# ESP_Server.net
KiCad netlist of a schematic drawn in EasyEDA
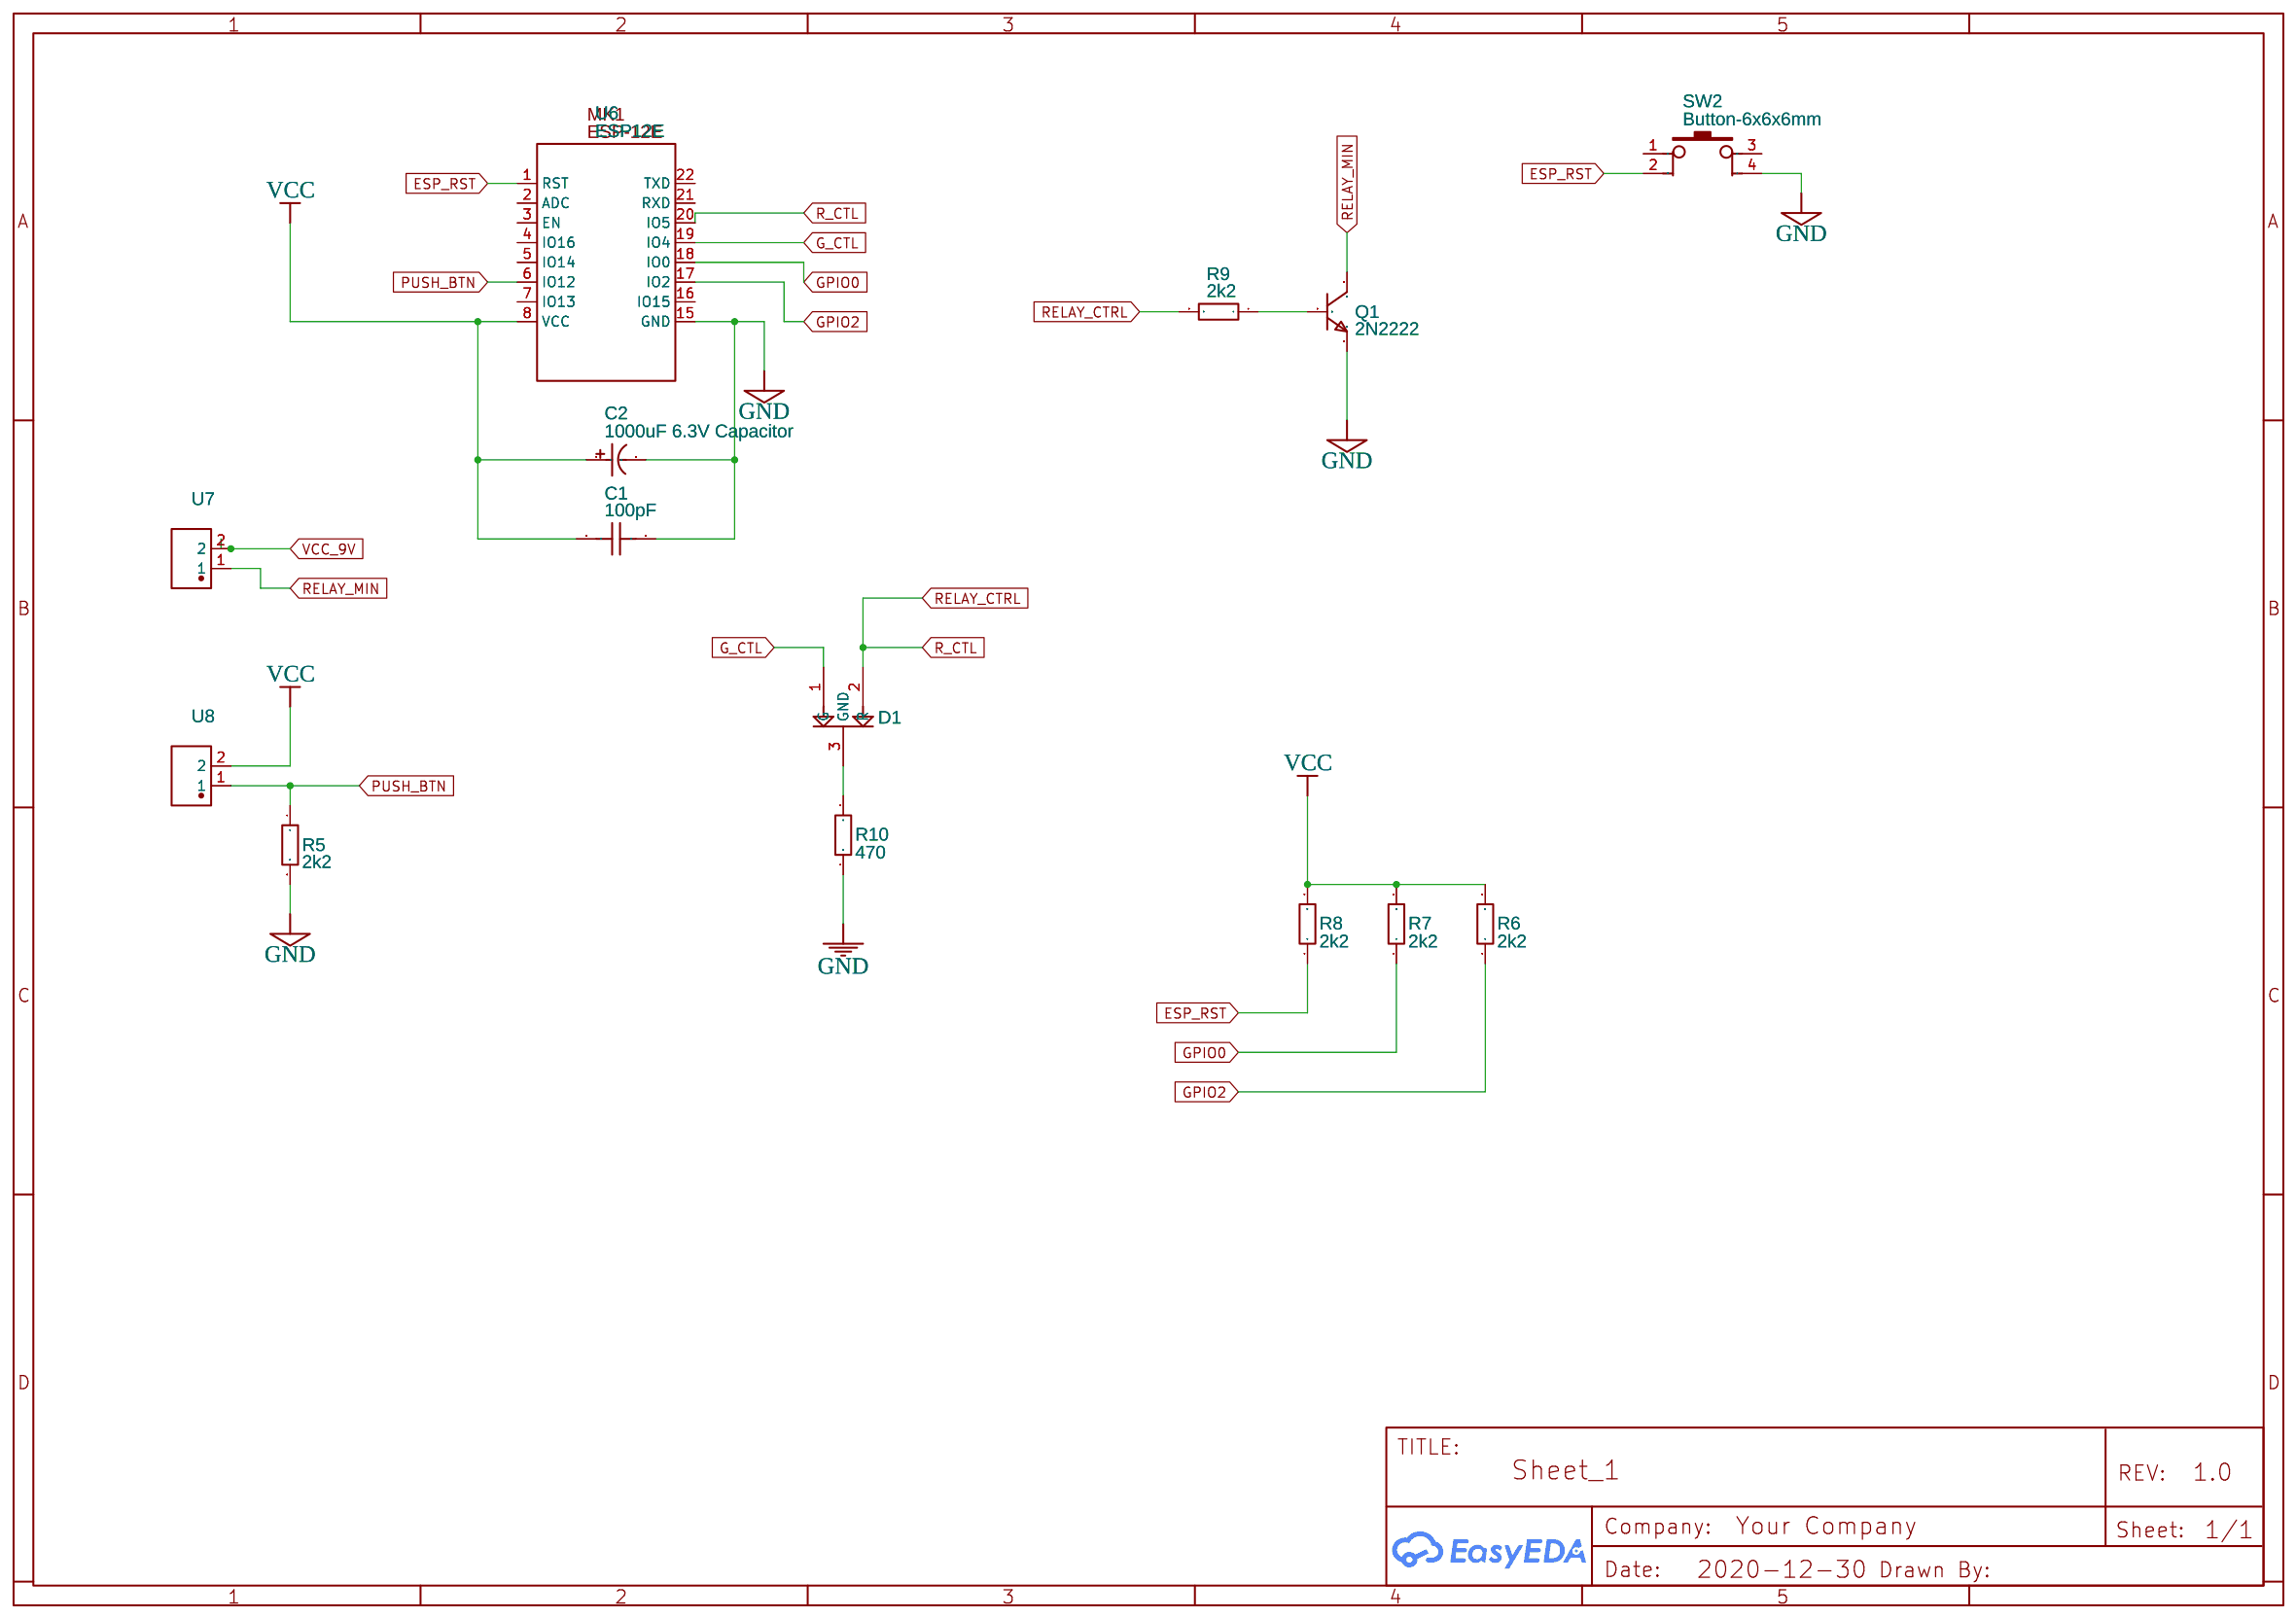
[diagram p0: schematic sheet]

(export (version "E")
  (design (tool "Eeschema 10.0.6"))
  (components
    (comp (ref "C1")
      (value "100pF")
      (fields
        (field (name "BOM_Manufacturer Part") "CC1H101KC74DSL4B10MN")
        (field (name "BOM_Supplier Part") "C254079")
      )
      (libsource (lib "") (part "CC1H101KC74DSL4B10MN"))
    )
    (comp (ref "C2") (value "1000uF 6.3V Capacitor") (libsource (lib "") (part "1000uF 6.3V Capacitor")))
    (comp (ref "D1")
      (value "RED GREEN CATODO")
      (fields (field (name "BOM_Manufacturer Part") "RG309WK-C"))
      (libsource (lib "") (part "RED GREEN CATODO"))
    )
    (comp (ref "Q1")
      (value "2N2222")
      (fields (field (name "BOM_Supplier Part") "C118536"))
      (libsource (lib "") (part "2N2222"))
    )
    (comp (ref "R5")
      (value "2k2")
      (fields
        (field (name "BOM_Manufacturer Part") "CFR02SJ0220A10")
        (field (name "BOM_Supplier Part") "C69874")
      )
      (libsource (lib "") (part "2k2_2"))
    )
    (comp (ref "R6")
      (value "2k2")
      (fields
        (field (name "BOM_Manufacturer Part") "CFR02SJ0220A10")
        (field (name "BOM_Supplier Part") "C69874")
      )
      (libsource (lib "") (part "2k2_1"))
    )
    (comp (ref "R7")
      (value "2k2")
      (fields
        (field (name "BOM_Manufacturer Part") "CFR02SJ0220A10")
        (field (name "BOM_Supplier Part") "C69874")
      )
      (libsource (lib "") (part "2k2_1"))
    )
    (comp (ref "R8")
      (value "2k2")
      (fields
        (field (name "BOM_Manufacturer Part") "CFR02SJ0220A10")
        (field (name "BOM_Supplier Part") "C69874")
      )
      (libsource (lib "") (part "2k2_1"))
    )
    (comp (ref "R9")
      (value "2k2")
      (fields
        (field (name "BOM_Manufacturer Part") "CFR02SJ0220A10")
        (field (name "BOM_Supplier Part") "C69874")
      )
      (libsource (lib "") (part "2k2"))
    )
    (comp (ref "R10")
      (value "470")
      (fields
        (field (name "BOM_Manufacturer Part") "MFR0W4F4700A50")
        (field (name "BOM_Supplier Part") "C58592")
      )
      (libsource (lib "") (part "47Ω"))
    )
    (comp (ref "SW2")
      (value "Button-6x6x6mm")
      (fields
        (field (name "BOM_Manufacturer Part") "Switch,6*6*6Plastic head,260G, 0.25mm,Straight line")
        (field (name "BOM_Supplier Part") "C71836")
      )
      (libsource (lib "") (part "Button-6x6x6mm"))
    )
    (comp (ref "U6") (value "ESP12E") (libsource (lib "") (part "ESP12E")))
    (comp (ref "U7")
      (value "XY301V-A-5.0-2P")
      (fields (field (name "BOM_Supplier Part") "C557651"))
      (libsource (lib "") (part "XY301V-A-5.0-2P"))
    )
    (comp (ref "U8")
      (value "XY301V-A-5.0-2P")
      (fields (field (name "BOM_Supplier Part") "C557651"))
      (libsource (lib "") (part "XY301V-A-5.0-2P"))
    )
  )
  (nets
    (net (code "1") (name "ESP_RST") (class "Default")
      (node (ref "R8") (pin "1") (pinfunction "1_1") (pintype "input"))
      (node (ref "SW2") (pin "2") (pinfunction "2_2") (pintype "input"))
      (node (ref "U6") (pin "1") (pinfunction "RST_1") (pintype "unspecified"))
    )
    (net (code "2") (name "GND") (class "Default")
      (node (ref "C1") (pin "2") (pinfunction "2_2") (pintype "unspecified"))
      (node (ref "C2") (pin "2") (pinfunction "2_2") (pintype "input"))
      (node (ref "Q1") (pin "1") (pinfunction "E_1") (pintype "unspecified"))
      (node (ref "R10") (pin "1") (pinfunction "1_1") (pintype "input"))
      (node (ref "R5") (pin "2") (pinfunction "2_2") (pintype "input"))
      (node (ref "SW2") (pin "4") (pinfunction "4_4") (pintype "input"))
      (node (ref "U6") (pin "15") (pinfunction "GND_15") (pintype "unspecified"))
    )
    (net (code "3") (name "GPIO0") (class "Default")
      (node (ref "R7") (pin "1") (pinfunction "1_1") (pintype "input"))
      (node (ref "U6") (pin "18") (pinfunction "IO0_18") (pintype "unspecified"))
    )
    (net (code "4") (name "GPIO2") (class "Default")
      (node (ref "R6") (pin "1") (pinfunction "1_1") (pintype "input"))
      (node (ref "U6") (pin "17") (pinfunction "IO2_17") (pintype "unspecified"))
    )
    (net (code "5") (name "G_CTL") (class "Default")
      (node (ref "D1") (pin "1") (pinfunction "G_1") (pintype "unspecified"))
      (node (ref "U6") (pin "19") (pinfunction "IO4_19") (pintype "unspecified"))
    )
    (net (code "6") (name "Net-(D1-GND)") (class "Default")
      (node (ref "D1") (pin "3") (pinfunction "GND_3") (pintype "unspecified"))
      (node (ref "R10") (pin "2") (pinfunction "2_2") (pintype "input"))
    )
    (net (code "7") (name "Net-(Q1-B)") (class "Default")
      (node (ref "Q1") (pin "2") (pinfunction "B_2") (pintype "unspecified"))
      (node (ref "R9") (pin "1") (pinfunction "1_1") (pintype "input"))
    )
    (net (code "8") (name "PUSH_BTN") (class "Default")
      (node (ref "R5") (pin "1") (pinfunction "1_1") (pintype "input"))
      (node (ref "U6") (pin "6") (pinfunction "IO12_6") (pintype "unspecified"))
      (node (ref "U8") (pin "1") (pinfunction "1_1") (pintype "unspecified"))
    )
    (net (code "9") (name "RELAY_CTRL") (class "Default")
      (node (ref "D1") (pin "2") (pinfunction "R_2") (pintype "unspecified"))
      (node (ref "R9") (pin "2") (pinfunction "2_2") (pintype "input"))
      (node (ref "U6") (pin "20") (pinfunction "IO5_20") (pintype "unspecified"))
    )
    (net (code "10") (name "RELAY_MIN") (class "Default")
      (node (ref "Q1") (pin "3") (pinfunction "C_3") (pintype "unspecified"))
      (node (ref "U7") (pin "1") (pinfunction "1_1") (pintype "unspecified"))
    )
    (net (code "11") (name "VCC") (class "Default")
      (node (ref "C1") (pin "1") (pinfunction "1_1") (pintype "unspecified"))
      (node (ref "C2") (pin "1") (pinfunction "1_1") (pintype "input"))
      (node (ref "R6") (pin "2") (pinfunction "2_2") (pintype "input"))
      (node (ref "R7") (pin "2") (pinfunction "2_2") (pintype "input"))
      (node (ref "R8") (pin "2") (pinfunction "2_2") (pintype "input"))
      (node (ref "U6") (pin "8") (pinfunction "VCC_8") (pintype "unspecified"))
      (node (ref "U8") (pin "2") (pinfunction "2_2") (pintype "unspecified"))
    )
    (net (code "12") (name "VCC_9V") (class "Default")
      (node (ref "U7") (pin "2") (pinfunction "2_2") (pintype "unspecified"))
    )
    (net (code "13") (name "unconnected-(SW2-Pad1)") (class "Default")
      (node (ref "SW2") (pin "1") (pinfunction "1_1") (pintype "input"))
    )
    (net (code "14") (name "unconnected-(SW2-Pad3)") (class "Default")
      (node (ref "SW2") (pin "3") (pinfunction "3_3") (pintype "input"))
    )
    (net (code "15") (name "unconnected-(U6-ADC-Pad2)") (class "Default")
      (node (ref "U6") (pin "2") (pinfunction "ADC_2") (pintype "unspecified"))
    )
    (net (code "16") (name "unconnected-(U6-EN-Pad3)") (class "Default")
      (node (ref "U6") (pin "3") (pinfunction "EN_3") (pintype "unspecified"))
    )
    (net (code "17") (name "unconnected-(U6-IO13-Pad7)") (class "Default")
      (node (ref "U6") (pin "7") (pinfunction "IO13_7") (pintype "unspecified"))
    )
    (net (code "18") (name "unconnected-(U6-IO14-Pad5)") (class "Default")
      (node (ref "U6") (pin "5") (pinfunction "IO14_5") (pintype "unspecified"))
    )
    (net (code "19") (name "unconnected-(U6-IO15-Pad16)") (class "Default")
      (node (ref "U6") (pin "16") (pinfunction "IO15_16") (pintype "unspecified"))
    )
    (net (code "20") (name "unconnected-(U6-IO16-Pad4)") (class "Default")
      (node (ref "U6") (pin "4") (pinfunction "IO16_4") (pintype "unspecified"))
    )
    (net (code "21") (name "unconnected-(U6-RXD-Pad21)") (class "Default")
      (node (ref "U6") (pin "21") (pinfunction "RXD_21") (pintype "unspecified"))
    )
    (net (code "22") (name "unconnected-(U6-TXD-Pad22)") (class "Default")
      (node (ref "U6") (pin "22") (pinfunction "TXD_22") (pintype "unspecified"))
    )
  )
)
